# A4a_ESP12.net
KiCad netlist of a schematic drawn in EAGLE
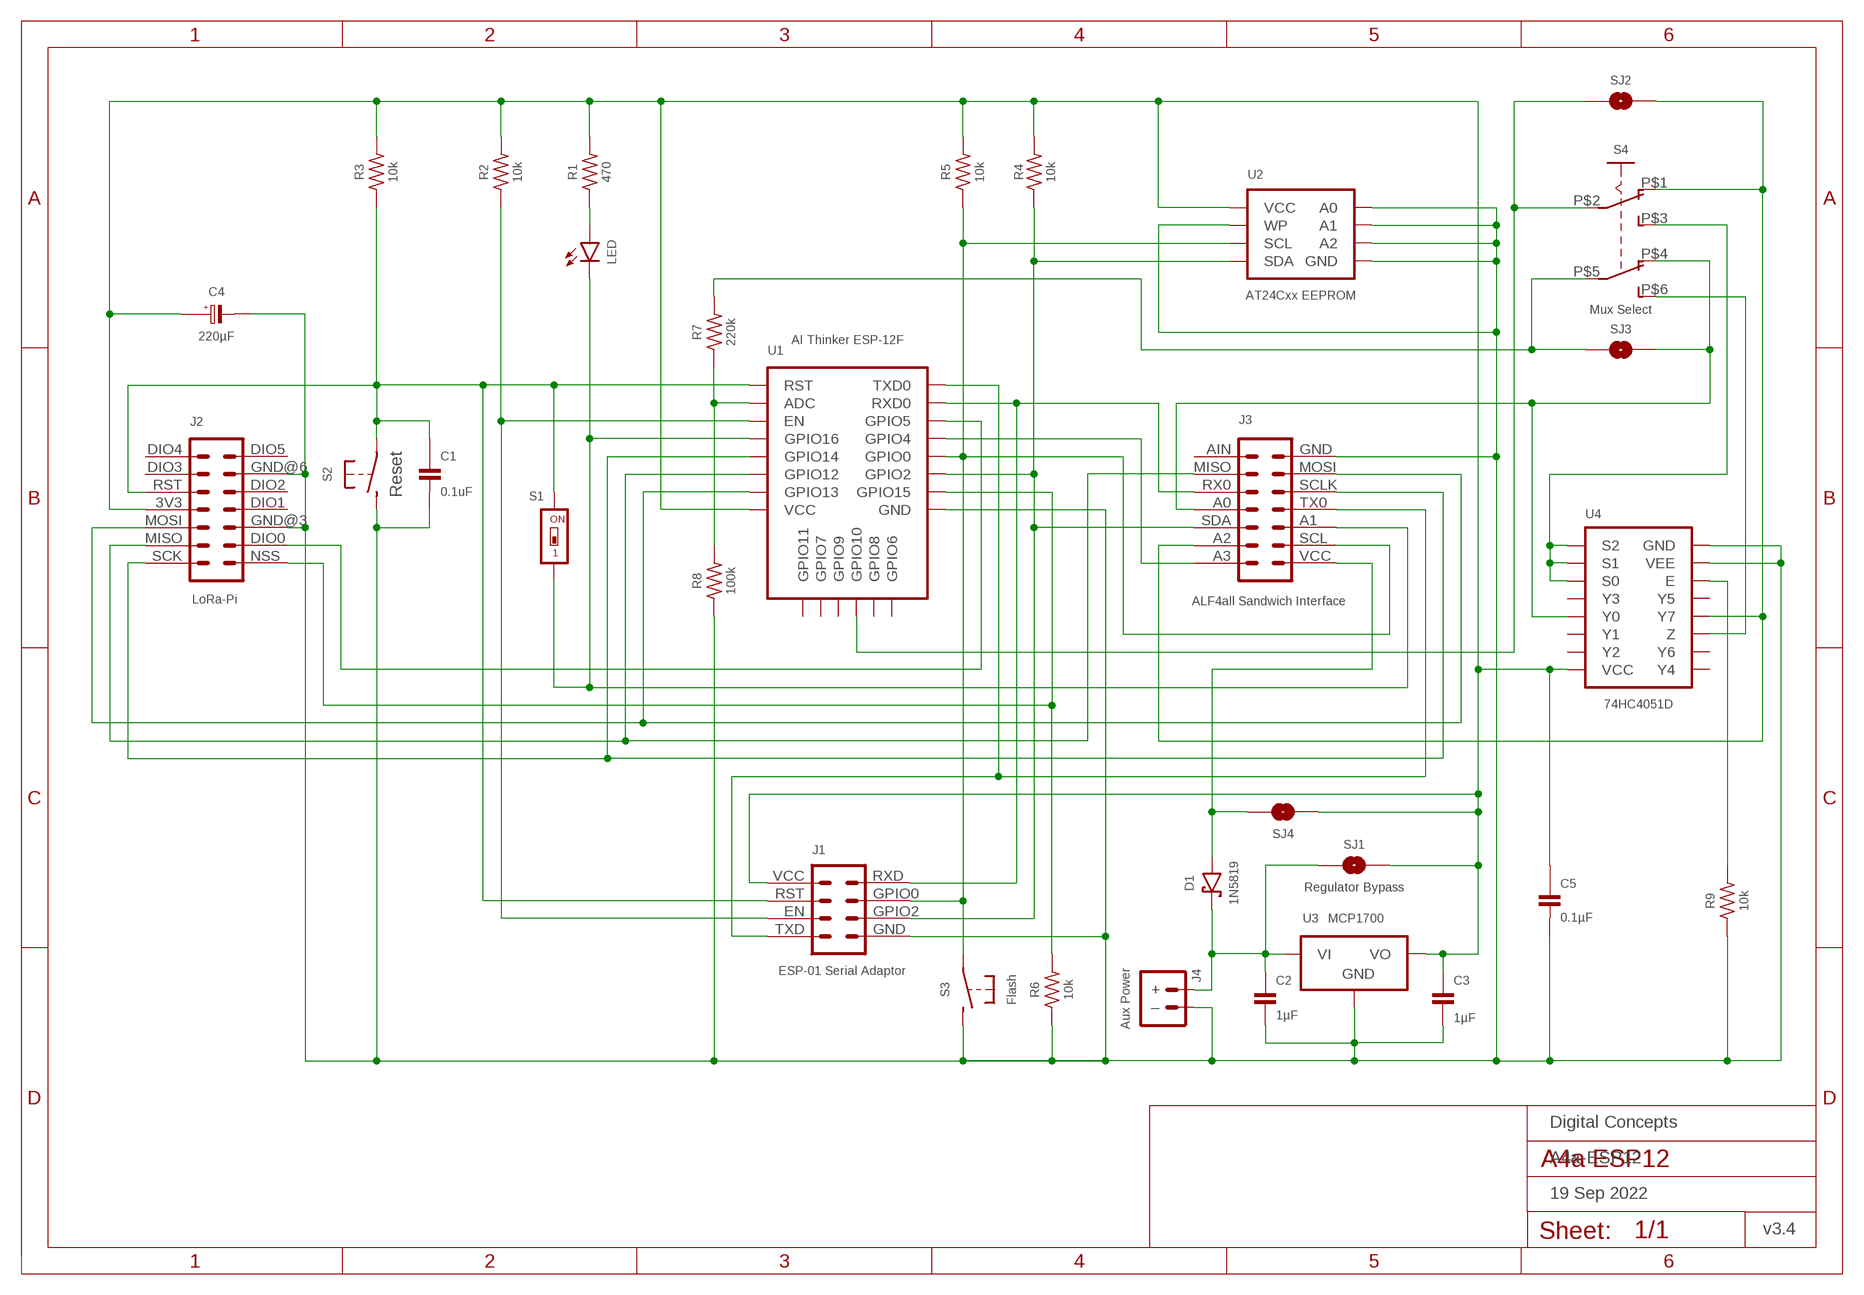
[diagram p0: schematic, sheet 1]

(export (version "E")
  (design (tool "Eeschema 10.0.6"))
  (components
    (comp (ref "C1")
      (value "0.1uF")
      (footprint "eagle-import:C0805")
      (libsource (lib "eagle-import") (part "CAPACITOR-0805"))
    )
    (comp (ref "C2")
      (value "1µF")
      (footprint "eagle-import:C0805@1")
      (libsource (lib "eagle-import") (part "CAPACITOR"))
    )
    (comp (ref "C3")
      (value "1µF")
      (footprint "eagle-import:C0805@1")
      (libsource (lib "eagle-import") (part "CAPACITOR"))
    )
    (comp (ref "C4")
      (value "220µF")
      (footprint "eagle-import:C3528-21")
      (libsource (lib "eagle-import") (part "CAPACITOR-TANTALUM-3528"))
    )
    (comp (ref "C5")
      (value "0.1µF")
      (footprint "eagle-import:C0805")
      (libsource (lib "eagle-import") (part "CAPACITOR-0805"))
    )
    (comp (ref "D1")
      (value "1N5819")
      (footprint "eagle-import:SOD-123")
      (libsource (lib "eagle-import") (part "DIODE-SCHOTTKY-1N5819"))
    )
    (comp (ref "J1")
      (value "ESP-01 Serial Adaptor")
      (footprint "eagle-import:CONN_2X4-ESP-01-SERIAL")
      (libsource (lib "eagle-import") (part "ESP-01-SERIAL-ADAPTOR"))
    )
    (comp (ref "J2")
      (value "LoRa-Pi")
      (footprint "eagle-import:RFM95W-PI")
      (libsource (lib "eagle-import") (part "RFM95W-PI-HEADER"))
    )
    (comp (ref "J3")
      (value "ALF4all Sandwich Interface")
      (footprint "eagle-import:CONN_2X7-ALF4ALL-PROCESSOR-B")
      (libsource (lib "eagle-import") (part "HEADER-2X7-ALF4ALL-PROCESSOR-B"))
    )
    (comp (ref "J4")
      (value "Aux Power")
      (footprint "eagle-import:JST-PH2.0-2-HORIZONTAL")
      (libsource (lib "eagle-import") (part "JST-PH2.0-2-MALE-HORIZONTALJST-PTH-2"))
    )
    (comp (ref "LED")
      (value "LEDCHIP-LED0805")
      (footprint "eagle-import:CHIP-LED0805")
      (libsource (lib "eagle-import") (part "LEDCHIP-LED0805"))
    )
    (comp (ref "R1")
      (value "470")
      (footprint "eagle-import:R0805")
      (libsource (lib "eagle-import") (part "RESISTORR0805"))
    )
    (comp (ref "R2")
      (value "10k")
      (footprint "eagle-import:R0805")
      (libsource (lib "eagle-import") (part "RESISTORR0805"))
    )
    (comp (ref "R3")
      (value "10k")
      (footprint "eagle-import:R0805")
      (libsource (lib "eagle-import") (part "RESISTORR0805"))
    )
    (comp (ref "R4")
      (value "10k")
      (footprint "eagle-import:R0805")
      (libsource (lib "eagle-import") (part "RESISTORR0805"))
    )
    (comp (ref "R5")
      (value "10k")
      (footprint "eagle-import:R0805")
      (libsource (lib "eagle-import") (part "RESISTORR0805"))
    )
    (comp (ref "R6")
      (value "10k")
      (footprint "eagle-import:R0805")
      (libsource (lib "eagle-import") (part "RESISTORR0805"))
    )
    (comp (ref "R7")
      (value "220k")
      (footprint "eagle-import:R0805")
      (libsource (lib "eagle-import") (part "RESISTORR0805"))
    )
    (comp (ref "R8")
      (value "100k")
      (footprint "eagle-import:R0805")
      (libsource (lib "eagle-import") (part "RESISTORR0805"))
    )
    (comp (ref "R9")
      (value "10k")
      (footprint "eagle-import:R0805")
      (libsource (lib "eagle-import") (part "RESISTORR0805"))
    )
    (comp (ref "S1")
      (value "Wake")
      (footprint "eagle-import:SMD-001")
      (libsource (lib "eagle-import") (part "SWITCH-DIP-SWS001"))
    )
    (comp (ref "S2")
      (value "Reset")
      (footprint "eagle-import:SWITCH-2-PAD")
      (libsource (lib "eagle-import") (part "SWITCH-MOMENTARY-2-PIN"))
    )
    (comp (ref "S3")
      (value "Flash")
      (footprint "eagle-import:SWITCH-2-PAD")
      (libsource (lib "eagle-import") (part "SWITCH-MOMENTARY-2-PIN"))
    )
    (comp (ref "S4")
      (value "Mux Select")
      (footprint "eagle-import:SWITCH-DPDT-SMD")
      (libsource (lib "eagle-import") (part "SWITCH-SLIDE-DPDT"))
    )
    (comp (ref "SJ1")
      (value "Regulator Bypass")
      (footprint "eagle-import:SJ")
      (libsource (lib "eagle-import") (part "SJ"))
    )
    (comp (ref "SJ2") (value "SJ") (footprint "eagle-import:SJ") (libsource (lib "eagle-import") (part "SJ")))
    (comp (ref "SJ3") (value "SJ") (footprint "eagle-import:SJ") (libsource (lib "eagle-import") (part "SJ")))
    (comp (ref "SJ4") (value "SJ") (footprint "eagle-import:SJ") (libsource (lib "eagle-import") (part "SJ")))
    (comp (ref "U1")
      (value "AI Thinker ESP-12F")
      (footprint "eagle-import:ESP-12E_F")
      (libsource (lib "eagle-import") (part "ESP-12E/F"))
    )
    (comp (ref "U2")
      (value "AT24Cxx EEPROM")
      (footprint "eagle-import:SOP-8")
      (libsource (lib "eagle-import") (part "AT24CXX-EEPROM"))
    )
    (comp (ref "U3")
      (value "MCP1700")
      (footprint "eagle-import:SOT-23-3")
      (libsource (lib "eagle-import") (part "MCP1700"))
    )
    (comp (ref "U4")
      (value "74HC4051D")
      (footprint "eagle-import:SOP16")
      (libsource (lib "eagle-import") (part "74HC4051D"))
    )
  )
  (nets
    (net (code "1") (name "Net-(C4-+)") (class "Default")
      (node (ref "C3") (pin "1") (pinfunction "1_1") (pintype "passive"))
      (node (ref "C4") (pin "1") (pinfunction "+_1") (pintype "passive"))
      (node (ref "C5") (pin "1") (pinfunction "1_1") (pintype "passive"))
      (node (ref "J1") (pin "VCC") (pinfunction "5_VCC") (pintype "passive"))
      (node (ref "J2") (pin "3V3") (pinfunction "11_3V3") (pintype "passive"))
      (node (ref "R1") (pin "2") (pinfunction "2_2") (pintype "passive"))
      (node (ref "R2") (pin "2") (pinfunction "2_2") (pintype "passive"))
      (node (ref "R3") (pin "2") (pinfunction "2_2") (pintype "passive"))
      (node (ref "R4") (pin "2") (pinfunction "2_2") (pintype "passive"))
      (node (ref "R5") (pin "2") (pinfunction "2_2") (pintype "passive"))
      (node (ref "SJ1") (pin "2") (pinfunction "2_2") (pintype "passive"))
      (node (ref "SJ4") (pin "2") (pinfunction "2_2") (pintype "passive"))
      (node (ref "U1") (pin "VCC") (pinfunction "VCC_VCC") (pintype "bidirectional"))
      (node (ref "U2") (pin "P$8") (pinfunction "VCC_P$8") (pintype "bidirectional"))
      (node (ref "U3") (pin "2") (pinfunction "VO_2") (pintype "output"))
      (node (ref "U4") (pin "16") (pinfunction "VCC_16") (pintype "bidirectional"))
    )
    (net (code "2") (name "Net-(C4--)") (class "Default")
      (node (ref "C1") (pin "2") (pinfunction "2_2") (pintype "passive"))
      (node (ref "C2") (pin "2") (pinfunction "2_2") (pintype "passive"))
      (node (ref "C3") (pin "2") (pinfunction "2_2") (pintype "passive"))
      (node (ref "C4") (pin "2") (pinfunction "-_2") (pintype "passive"))
      (node (ref "C5") (pin "2") (pinfunction "2_2") (pintype "passive"))
      (node (ref "J1") (pin "GND") (pinfunction "1_GND") (pintype "passive"))
      (node (ref "J2") (pin "GND@3") (pinfunction "3_GND@3") (pintype "passive"))
      (node (ref "J2") (pin "GND@6") (pinfunction "6_GND@6") (pintype "passive"))
      (node (ref "J3") (pin "GND") (pinfunction "7_GND") (pintype "passive"))
      (node (ref "J4") (pin "-") (pinfunction "–_-") (pintype "power_in"))
      (node (ref "R6") (pin "1") (pinfunction "1_1") (pintype "passive"))
      (node (ref "R8") (pin "1") (pinfunction "1_1") (pintype "passive"))
      (node (ref "R9") (pin "1") (pinfunction "1_1") (pintype "passive"))
      (node (ref "S2") (pin "P$2") (pinfunction "S_P$2") (pintype "passive"))
      (node (ref "S3") (pin "P$2") (pinfunction "S_P$2") (pintype "passive"))
      (node (ref "U1") (pin "GND") (pinfunction "GND_GND") (pintype "bidirectional"))
      (node (ref "U2") (pin "P$1") (pinfunction "A0_P$1") (pintype "bidirectional"))
      (node (ref "U2") (pin "P$2") (pinfunction "A1_P$2") (pintype "bidirectional"))
      (node (ref "U2") (pin "P$3") (pinfunction "A2_P$3") (pintype "bidirectional"))
      (node (ref "U2") (pin "P$4") (pinfunction "GND_P$4") (pintype "bidirectional"))
      (node (ref "U2") (pin "P$7") (pinfunction "WP_P$7") (pintype "bidirectional"))
      (node (ref "U3") (pin "1") (pinfunction "GND_1") (pintype "passive"))
      (node (ref "U4") (pin "7") (pinfunction "VEE_7") (pintype "bidirectional"))
      (node (ref "U4") (pin "8") (pinfunction "GND_8") (pintype "bidirectional"))
    )
    (net (code "3") (name "Net-(J1-2)") (class "Default")
      (node (ref "J1") (pin "GPIO2") (pinfunction "2_GPIO2") (pintype "passive"))
      (node (ref "J3") (pin "SDA") (pinfunction "12_SDA") (pintype "passive"))
      (node (ref "R4") (pin "1") (pinfunction "1_1") (pintype "passive"))
      (node (ref "U1") (pin "GPIO2") (pinfunction "GPIO2_GPIO2") (pintype "bidirectional"))
      (node (ref "U2") (pin "P$5") (pinfunction "SDA_P$5") (pintype "bidirectional"))
    )
    (net (code "4") (name "Net-(J1-3)") (class "Default")
      (node (ref "J1") (pin "GPIO0") (pinfunction "3_GPIO0") (pintype "passive"))
      (node (ref "J3") (pin "SCL") (pinfunction "2_SCL") (pintype "passive"))
      (node (ref "R5") (pin "1") (pinfunction "1_1") (pintype "passive"))
      (node (ref "S3") (pin "P$1") (pinfunction "P_P$1") (pintype "passive"))
      (node (ref "U1") (pin "GPIO0") (pinfunction "GPIO0_GPIO0") (pintype "bidirectional"))
      (node (ref "U2") (pin "P$6") (pinfunction "SCL_P$6") (pintype "bidirectional"))
    )
    (net (code "5") (name "Net-(J1-4)") (class "Default")
      (node (ref "J1") (pin "RXD") (pinfunction "4_RXD") (pintype "passive"))
      (node (ref "J3") (pin "RX0") (pinfunction "10_RX0") (pintype "passive"))
      (node (ref "U1") (pin "RXD0") (pinfunction "RXD0_RXD0") (pintype "bidirectional"))
    )
    (net (code "6") (name "Net-(J1-6)") (class "Default")
      (node (ref "C1") (pin "1") (pinfunction "1_1") (pintype "passive"))
      (node (ref "J1") (pin "RST") (pinfunction "6_RST") (pintype "passive"))
      (node (ref "J2") (pin "RST") (pinfunction "10_RST") (pintype "passive"))
      (node (ref "R3") (pin "1") (pinfunction "1_1") (pintype "passive"))
      (node (ref "S1") (pin "2") (pinfunction "2_2") (pintype "passive"))
      (node (ref "S2") (pin "P$1") (pinfunction "P_P$1") (pintype "passive"))
      (node (ref "U1") (pin "RST") (pinfunction "RST_RST") (pintype "bidirectional"))
    )
    (net (code "7") (name "Net-(J1-7)") (class "Default")
      (node (ref "J1") (pin "EN") (pinfunction "7_EN") (pintype "passive"))
      (node (ref "R2") (pin "1") (pinfunction "1_1") (pintype "passive"))
      (node (ref "U1") (pin "EN") (pinfunction "EN_EN") (pintype "bidirectional"))
    )
    (net (code "8") (name "Net-(J1-8)") (class "Default")
      (node (ref "J1") (pin "TXD") (pinfunction "8_TXD") (pintype "passive"))
      (node (ref "J3") (pin "TX0") (pinfunction "4_TX0") (pintype "passive"))
      (node (ref "U1") (pin "TXD0") (pinfunction "TXD0_TXD0") (pintype "bidirectional"))
    )
    (net (code "9") (name "Net-(J2-1)") (class "Default")
      (node (ref "J2") (pin "NSS") (pinfunction "1_NSS") (pintype "passive"))
      (node (ref "R6") (pin "2") (pinfunction "2_2") (pintype "passive"))
      (node (ref "U1") (pin "GPIO15") (pinfunction "GPIO15_GPIO15") (pintype "bidirectional"))
    )
    (net (code "10") (name "Net-(J2-2)") (class "Default")
      (node (ref "J2") (pin "DIO0") (pinfunction "2_DIO0") (pintype "passive"))
      (node (ref "U1") (pin "GPIO5") (pinfunction "GPIO5_GPIO5") (pintype "bidirectional"))
    )
    (net (code "11") (name "Net-(J2-12)") (class "Default")
      (node (ref "J2") (pin "MOSI") (pinfunction "12_MOSI") (pintype "passive"))
      (node (ref "J3") (pin "MOSI") (pinfunction "6_MOSI") (pintype "passive"))
      (node (ref "U1") (pin "GPIO13") (pinfunction "GPIO13_GPIO13") (pintype "bidirectional"))
    )
    (net (code "12") (name "Net-(J2-13)") (class "Default")
      (node (ref "J2") (pin "MISO") (pinfunction "13_MISO") (pintype "passive"))
      (node (ref "J3") (pin "MISO") (pinfunction "9_MISO") (pintype "passive"))
      (node (ref "U1") (pin "GPIO12") (pinfunction "GPIO12_GPIO12") (pintype "bidirectional"))
    )
    (net (code "13") (name "Net-(J2-14)") (class "Default")
      (node (ref "J2") (pin "SCK") (pinfunction "14_SCK") (pintype "passive"))
      (node (ref "J3") (pin "SCLK") (pinfunction "5_SCLK") (pintype "passive"))
      (node (ref "U1") (pin "GPIO14") (pinfunction "GPIO14_GPIO14") (pintype "bidirectional"))
    )
    (net (code "14") (name "Net-(J3-1)") (class "Default")
      (node (ref "D1") (pin "A") (pinfunction "A_A") (pintype "passive"))
      (node (ref "J3") (pin "VCC") (pinfunction "1_VCC") (pintype "passive"))
      (node (ref "SJ4") (pin "1") (pinfunction "1_1") (pintype "passive"))
    )
    (net (code "15") (name "Net-(J3-3)") (class "Default")
      (node (ref "J3") (pin "A1") (pinfunction "3_A1") (pintype "passive"))
      (node (ref "LED") (pin "C") (pinfunction "C_C") (pintype "passive"))
      (node (ref "S1") (pin "1") (pinfunction "1_1") (pintype "passive"))
      (node (ref "U1") (pin "GPIO16") (pinfunction "GPIO16_GPIO16") (pintype "bidirectional"))
    )
    (net (code "16") (name "Net-(J3-11)") (class "Default")
      (node (ref "J3") (pin "A0") (pinfunction "11_A0") (pintype "passive"))
      (node (ref "S4") (pin "P$4") (pinfunction "O2_P$4") (pintype "passive"))
      (node (ref "SJ3") (pin "2") (pinfunction "2_2") (pintype "passive"))
      (node (ref "U4") (pin "13") (pinfunction "Y0_13") (pintype "bidirectional"))
    )
    (net (code "17") (name "Net-(J3-13)") (class "Default")
      (node (ref "J3") (pin "A2") (pinfunction "13_A2") (pintype "passive"))
      (node (ref "S4") (pin "P$1") (pinfunction "O1_P$1") (pintype "passive"))
      (node (ref "SJ2") (pin "2") (pinfunction "2_2") (pintype "passive"))
      (node (ref "U4") (pin "4") (pinfunction "Y7_4") (pintype "bidirectional"))
    )
    (net (code "18") (name "Net-(J3-14)") (class "Default")
      (node (ref "J3") (pin "A3") (pinfunction "14_A3") (pintype "passive"))
      (node (ref "U1") (pin "GPIO4") (pinfunction "GPIO4_GPIO4") (pintype "bidirectional"))
    )
    (net (code "19") (name "Net-(LED-PadA)") (class "Default")
      (node (ref "LED") (pin "A") (pinfunction "A_A") (pintype "passive"))
      (node (ref "R1") (pin "1") (pinfunction "1_1") (pintype "passive"))
    )
    (net (code "20") (name "Net-(R7-Pad1)") (class "Default")
      (node (ref "R7") (pin "1") (pinfunction "1_1") (pintype "passive"))
      (node (ref "R8") (pin "2") (pinfunction "2_2") (pintype "passive"))
      (node (ref "U1") (pin "ADC") (pinfunction "ADC_ADC") (pintype "bidirectional"))
    )
    (net (code "21") (name "Net-(S4-P1)") (class "Default")
      (node (ref "S4") (pin "P$2") (pinfunction "P1_P$2") (pintype "passive"))
      (node (ref "SJ2") (pin "1") (pinfunction "1_1") (pintype "passive"))
      (node (ref "U1") (pin "GPIO10") (pinfunction "GPIO10_GPIO10") (pintype "bidirectional"))
    )
    (net (code "22") (name "Net-(S4-P2)") (class "Default")
      (node (ref "R7") (pin "2") (pinfunction "2_2") (pintype "passive"))
      (node (ref "S4") (pin "P$5") (pinfunction "P2_P$5") (pintype "passive"))
      (node (ref "SJ3") (pin "1") (pinfunction "1_1") (pintype "passive"))
    )
    (net (code "23") (name "Net-(S4-S1)") (class "Default")
      (node (ref "S4") (pin "P$3") (pinfunction "S1_P$3") (pintype "passive"))
      (node (ref "U4") (pin "10") (pinfunction "S1_10") (pintype "bidirectional"))
      (node (ref "U4") (pin "11") (pinfunction "S0_11") (pintype "bidirectional"))
      (node (ref "U4") (pin "9") (pinfunction "S2_9") (pintype "bidirectional"))
    )
    (net (code "24") (name "Net-(S4-S2)") (class "Default")
      (node (ref "S4") (pin "P$6") (pinfunction "S2_P$6") (pintype "passive"))
      (node (ref "U4") (pin "3") (pinfunction "Z_3") (pintype "bidirectional"))
    )
    (net (code "25") (name "Net-(U3-VI)") (class "Default")
      (node (ref "C2") (pin "1") (pinfunction "1_1") (pintype "passive"))
      (node (ref "D1") (pin "C") (pinfunction "C_C") (pintype "passive"))
      (node (ref "J4") (pin "+") (pinfunction "+_+") (pintype "power_in"))
      (node (ref "SJ1") (pin "1") (pinfunction "1_1") (pintype "passive"))
      (node (ref "U3") (pin "3") (pinfunction "VI_3") (pintype "input"))
    )
    (net (code "26") (name "Net-(U4-E)") (class "Default")
      (node (ref "R9") (pin "2") (pinfunction "2_2") (pintype "passive"))
      (node (ref "U4") (pin "6") (pinfunction "E_6") (pintype "bidirectional"))
    )
    (net (code "27") (name "unconnected-(J2-4-PadDIO1)") (class "Default")
      (node (ref "J2") (pin "DIO1") (pinfunction "4_DIO1") (pintype "passive"))
    )
    (net (code "28") (name "unconnected-(J2-5-PadDIO2)") (class "Default")
      (node (ref "J2") (pin "DIO2") (pinfunction "5_DIO2") (pintype "passive"))
    )
    (net (code "29") (name "unconnected-(J2-7-PadDIO5)") (class "Default")
      (node (ref "J2") (pin "DIO5") (pinfunction "7_DIO5") (pintype "passive"))
    )
    (net (code "30") (name "unconnected-(J2-8-PadDIO4)") (class "Default")
      (node (ref "J2") (pin "DIO4") (pinfunction "8_DIO4") (pintype "passive"))
    )
    (net (code "31") (name "unconnected-(J2-9-PadDIO3)") (class "Default")
      (node (ref "J2") (pin "DIO3") (pinfunction "9_DIO3") (pintype "passive"))
    )
    (net (code "32") (name "unconnected-(J3-8-PadAIN)") (class "Default")
      (node (ref "J3") (pin "AIN") (pinfunction "8_AIN") (pintype "passive"))
    )
    (net (code "33") (name "unconnected-(U1-GPIO6-PadSCLK)") (class "Default")
      (node (ref "U1") (pin "SCLK") (pinfunction "GPIO6_SCLK") (pintype "bidirectional"))
    )
    (net (code "34") (name "unconnected-(U1-GPIO7-PadMISO)") (class "Default")
      (node (ref "U1") (pin "MISO") (pinfunction "GPIO7_MISO") (pintype "bidirectional"))
    )
    (net (code "35") (name "unconnected-(U1-GPIO8-PadMOSI)") (class "Default")
      (node (ref "U1") (pin "MOSI") (pinfunction "GPIO8_MOSI") (pintype "bidirectional"))
    )
    (net (code "36") (name "unconnected-(U1-GPIO11-PadCS0)") (class "Default")
      (node (ref "U1") (pin "CS0") (pinfunction "GPIO11_CS0") (pintype "bidirectional"))
    )
    (net (code "37") (name "unconnected-(U1-PadGPIO9)") (class "Default")
      (node (ref "U1") (pin "GPIO9") (pinfunction "GPIO9_GPIO9") (pintype "bidirectional"))
    )
    (net (code "38") (name "unconnected-(U4-Y1-Pad14)") (class "Default")
      (node (ref "U4") (pin "14") (pinfunction "Y1_14") (pintype "bidirectional"))
    )
    (net (code "39") (name "unconnected-(U4-Y2-Pad15)") (class "Default")
      (node (ref "U4") (pin "15") (pinfunction "Y2_15") (pintype "bidirectional"))
    )
    (net (code "40") (name "unconnected-(U4-Y3-Pad12)") (class "Default")
      (node (ref "U4") (pin "12") (pinfunction "Y3_12") (pintype "bidirectional"))
    )
    (net (code "41") (name "unconnected-(U4-Y4-Pad1)") (class "Default")
      (node (ref "U4") (pin "1") (pinfunction "Y4_1") (pintype "bidirectional"))
    )
    (net (code "42") (name "unconnected-(U4-Y5-Pad5)") (class "Default")
      (node (ref "U4") (pin "5") (pinfunction "Y5_5") (pintype "bidirectional"))
    )
    (net (code "43") (name "unconnected-(U4-Y6-Pad2)") (class "Default")
      (node (ref "U4") (pin "2") (pinfunction "Y6_2") (pintype "bidirectional"))
    )
  )
)
